# Prophesse_Sensor_v_1_5.net
KiCad netlist of a schematic drawn in Altium Designer
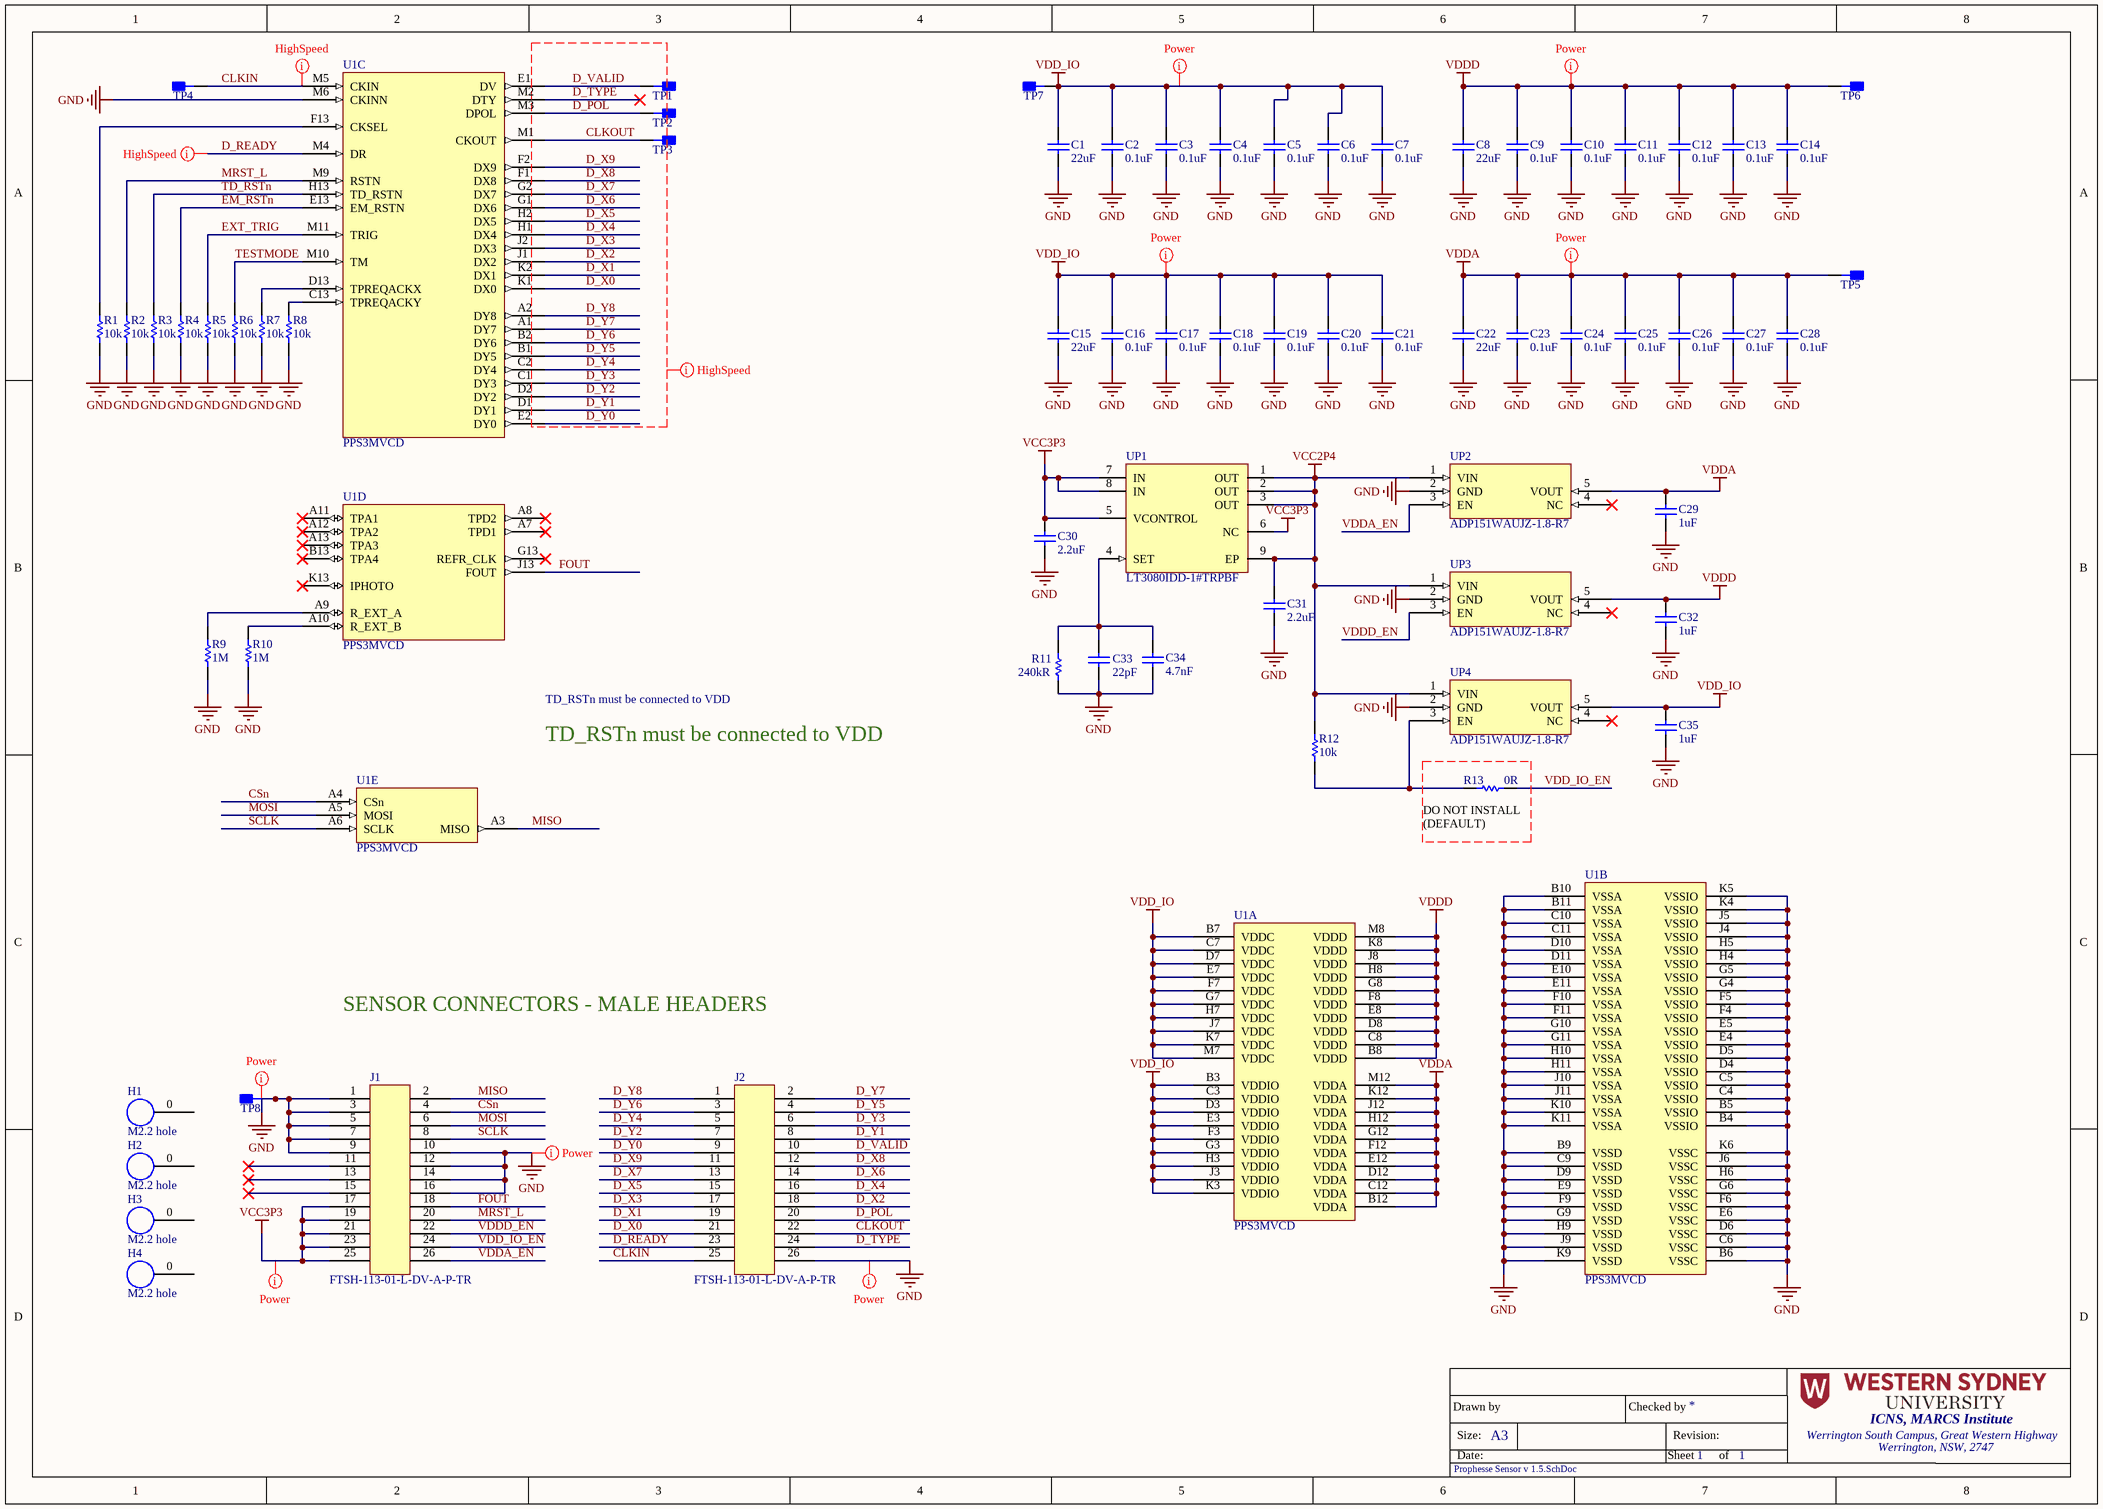
[diagram p0: Prophesse Sensor v 1.5.SchDoc]

(export (version "E")
  (design (tool "Eeschema 10.0.6"))
  (components
    (comp (ref "C1")
      (value "22uF")
      (footprint "CAP 0603 (1608)")
      (fields
        (field (name "MANUFACTURER") "Taiyo Yuden")
        (field (name "MANUFACTURER PART NUMBER") "LMK107BBJ226MA-T")
      )
      (libsource (lib "Falcon_Neuro") (part "LMK107BBJ226MA-T"))
    )
    (comp (ref "C2")
      (value "0.1uF")
      (footprint "CAP 0201 (0603)")
      (description "C0201C104K9PACTU, 0.1µF ±10% 6.3V Ceramic Capacitor X5R 0201 (0603 Metric)")
      (fields
        (field (name "MANUFACTURER") "KENET")
        (field (name "MANUFACTURER PART NUMBER") "C0201C104K9PACTU")
      )
      (libsource (lib "Falcon_Neuro") (part "C0201C104K9PACTU"))
    )
    (comp (ref "C3")
      (value "0.1uF")
      (footprint "CAP 0201 (0603)")
      (description "C0201C104K9PACTU, 0.1µF ±10% 6.3V Ceramic Capacitor X5R 0201 (0603 Metric)")
      (fields
        (field (name "MANUFACTURER") "KENET")
        (field (name "MANUFACTURER PART NUMBER") "C0201C104K9PACTU")
      )
      (libsource (lib "Falcon_Neuro") (part "C0201C104K9PACTU"))
    )
    (comp (ref "C4")
      (value "0.1uF")
      (footprint "CAP 0201 (0603)")
      (description "C0201C104K9PACTU, 0.1µF ±10% 6.3V Ceramic Capacitor X5R 0201 (0603 Metric)")
      (fields
        (field (name "MANUFACTURER") "KENET")
        (field (name "MANUFACTURER PART NUMBER") "C0201C104K9PACTU")
      )
      (libsource (lib "Falcon_Neuro") (part "C0201C104K9PACTU"))
    )
    (comp (ref "C5")
      (value "0.1uF")
      (footprint "CAP 0201 (0603)")
      (description "C0201C104K9PACTU, 0.1µF ±10% 6.3V Ceramic Capacitor X5R 0201 (0603 Metric)")
      (fields
        (field (name "MANUFACTURER") "KENET")
        (field (name "MANUFACTURER PART NUMBER") "C0201C104K9PACTU")
      )
      (libsource (lib "Falcon_Neuro") (part "C0201C104K9PACTU"))
    )
    (comp (ref "C6")
      (value "0.1uF")
      (footprint "CAP 0201 (0603)")
      (description "C0201C104K9PACTU, 0.1µF ±10% 6.3V Ceramic Capacitor X5R 0201 (0603 Metric)")
      (fields
        (field (name "MANUFACTURER") "KENET")
        (field (name "MANUFACTURER PART NUMBER") "C0201C104K9PACTU")
      )
      (libsource (lib "Falcon_Neuro") (part "C0201C104K9PACTU"))
    )
    (comp (ref "C7")
      (value "0.1uF")
      (footprint "CAP 0201 (0603)")
      (description "C0201C104K9PACTU, 0.1µF ±10% 6.3V Ceramic Capacitor X5R 0201 (0603 Metric)")
      (fields
        (field (name "MANUFACTURER") "KENET")
        (field (name "MANUFACTURER PART NUMBER") "C0201C104K9PACTU")
      )
      (libsource (lib "Falcon_Neuro") (part "C0201C104K9PACTU"))
    )
    (comp (ref "C8")
      (value "22uF")
      (footprint "CAP 0603 (1608)")
      (fields
        (field (name "MANUFACTURER") "Taiyo Yuden")
        (field (name "MANUFACTURER PART NUMBER") "LMK107BBJ226MA-T")
      )
      (libsource (lib "Falcon_Neuro") (part "LMK107BBJ226MA-T"))
    )
    (comp (ref "C9")
      (value "0.1uF")
      (footprint "CAP 0201 (0603)")
      (description "C0201C104K9PACTU, 0.1µF ±10% 6.3V Ceramic Capacitor X5R 0201 (0603 Metric)")
      (fields
        (field (name "MANUFACTURER") "KENET")
        (field (name "MANUFACTURER PART NUMBER") "C0201C104K9PACTU")
      )
      (libsource (lib "Falcon_Neuro") (part "C0201C104K9PACTU"))
    )
    (comp (ref "C10")
      (value "0.1uF")
      (footprint "CAP 0201 (0603)")
      (description "C0201C104K9PACTU, 0.1µF ±10% 6.3V Ceramic Capacitor X5R 0201 (0603 Metric)")
      (fields
        (field (name "MANUFACTURER") "KENET")
        (field (name "MANUFACTURER PART NUMBER") "C0201C104K9PACTU")
      )
      (libsource (lib "Falcon_Neuro") (part "C0201C104K9PACTU"))
    )
    (comp (ref "C11")
      (value "0.1uF")
      (footprint "CAP 0201 (0603)")
      (description "C0201C104K9PACTU, 0.1µF ±10% 6.3V Ceramic Capacitor X5R 0201 (0603 Metric)")
      (fields
        (field (name "MANUFACTURER") "KENET")
        (field (name "MANUFACTURER PART NUMBER") "C0201C104K9PACTU")
      )
      (libsource (lib "Falcon_Neuro") (part "C0201C104K9PACTU"))
    )
    (comp (ref "C12")
      (value "0.1uF")
      (footprint "CAP 0201 (0603)")
      (description "C0201C104K9PACTU, 0.1µF ±10% 6.3V Ceramic Capacitor X5R 0201 (0603 Metric)")
      (fields
        (field (name "MANUFACTURER") "KENET")
        (field (name "MANUFACTURER PART NUMBER") "C0201C104K9PACTU")
      )
      (libsource (lib "Falcon_Neuro") (part "C0201C104K9PACTU"))
    )
    (comp (ref "C13")
      (value "0.1uF")
      (footprint "CAP 0201 (0603)")
      (description "C0201C104K9PACTU, 0.1µF ±10% 6.3V Ceramic Capacitor X5R 0201 (0603 Metric)")
      (fields
        (field (name "MANUFACTURER") "KENET")
        (field (name "MANUFACTURER PART NUMBER") "C0201C104K9PACTU")
      )
      (libsource (lib "Falcon_Neuro") (part "C0201C104K9PACTU"))
    )
    (comp (ref "C14")
      (value "0.1uF")
      (footprint "CAP 0201 (0603)")
      (description "C0201C104K9PACTU, 0.1µF ±10% 6.3V Ceramic Capacitor X5R 0201 (0603 Metric)")
      (fields
        (field (name "MANUFACTURER") "KENET")
        (field (name "MANUFACTURER PART NUMBER") "C0201C104K9PACTU")
      )
      (libsource (lib "Falcon_Neuro") (part "C0201C104K9PACTU"))
    )
    (comp (ref "C15")
      (value "22uF")
      (footprint "CAP 0603 (1608)")
      (fields
        (field (name "MANUFACTURER") "Taiyo Yuden")
        (field (name "MANUFACTURER PART NUMBER") "LMK107BBJ226MA-T")
      )
      (libsource (lib "Falcon_Neuro") (part "LMK107BBJ226MA-T"))
    )
    (comp (ref "C16")
      (value "0.1uF")
      (footprint "CAP 0201 (0603)")
      (description "C0201C104K9PACTU, 0.1µF ±10% 6.3V Ceramic Capacitor X5R 0201 (0603 Metric)")
      (fields
        (field (name "MANUFACTURER") "KENET")
        (field (name "MANUFACTURER PART NUMBER") "C0201C104K9PACTU")
      )
      (libsource (lib "Falcon_Neuro") (part "C0201C104K9PACTU"))
    )
    (comp (ref "C17")
      (value "0.1uF")
      (footprint "CAP 0201 (0603)")
      (description "C0201C104K9PACTU, 0.1µF ±10% 6.3V Ceramic Capacitor X5R 0201 (0603 Metric)")
      (fields
        (field (name "MANUFACTURER") "KENET")
        (field (name "MANUFACTURER PART NUMBER") "C0201C104K9PACTU")
      )
      (libsource (lib "Falcon_Neuro") (part "C0201C104K9PACTU"))
    )
    (comp (ref "C18")
      (value "0.1uF")
      (footprint "CAP 0201 (0603)")
      (description "C0201C104K9PACTU, 0.1µF ±10% 6.3V Ceramic Capacitor X5R 0201 (0603 Metric)")
      (fields
        (field (name "MANUFACTURER") "KENET")
        (field (name "MANUFACTURER PART NUMBER") "C0201C104K9PACTU")
      )
      (libsource (lib "Falcon_Neuro") (part "C0201C104K9PACTU"))
    )
    (comp (ref "C19")
      (value "0.1uF")
      (footprint "CAP 0201 (0603)")
      (description "C0201C104K9PACTU, 0.1µF ±10% 6.3V Ceramic Capacitor X5R 0201 (0603 Metric)")
      (fields
        (field (name "MANUFACTURER") "KENET")
        (field (name "MANUFACTURER PART NUMBER") "C0201C104K9PACTU")
      )
      (libsource (lib "Falcon_Neuro") (part "C0201C104K9PACTU"))
    )
    (comp (ref "C20")
      (value "0.1uF")
      (footprint "CAP 0201 (0603)")
      (description "C0201C104K9PACTU, 0.1µF ±10% 6.3V Ceramic Capacitor X5R 0201 (0603 Metric)")
      (fields
        (field (name "MANUFACTURER") "KENET")
        (field (name "MANUFACTURER PART NUMBER") "C0201C104K9PACTU")
      )
      (libsource (lib "Falcon_Neuro") (part "C0201C104K9PACTU"))
    )
    (comp (ref "C21")
      (value "0.1uF")
      (footprint "CAP 0201 (0603)")
      (description "C0201C104K9PACTU, 0.1µF ±10% 6.3V Ceramic Capacitor X5R 0201 (0603 Metric)")
      (fields
        (field (name "MANUFACTURER") "KENET")
        (field (name "MANUFACTURER PART NUMBER") "C0201C104K9PACTU")
      )
      (libsource (lib "Falcon_Neuro") (part "C0201C104K9PACTU"))
    )
    (comp (ref "C22")
      (value "22uF")
      (footprint "CAP 0603 (1608)")
      (fields
        (field (name "MANUFACTURER") "Taiyo Yuden")
        (field (name "MANUFACTURER PART NUMBER") "LMK107BBJ226MA-T")
      )
      (libsource (lib "Falcon_Neuro") (part "LMK107BBJ226MA-T"))
    )
    (comp (ref "C23")
      (value "0.1uF")
      (footprint "CAP 0201 (0603)")
      (description "C0201C104K9PACTU, 0.1µF ±10% 6.3V Ceramic Capacitor X5R 0201 (0603 Metric)")
      (fields
        (field (name "MANUFACTURER") "KENET")
        (field (name "MANUFACTURER PART NUMBER") "C0201C104K9PACTU")
      )
      (libsource (lib "Falcon_Neuro") (part "C0201C104K9PACTU"))
    )
    (comp (ref "C24")
      (value "0.1uF")
      (footprint "CAP 0201 (0603)")
      (description "C0201C104K9PACTU, 0.1µF ±10% 6.3V Ceramic Capacitor X5R 0201 (0603 Metric)")
      (fields
        (field (name "MANUFACTURER") "KENET")
        (field (name "MANUFACTURER PART NUMBER") "C0201C104K9PACTU")
      )
      (libsource (lib "Falcon_Neuro") (part "C0201C104K9PACTU"))
    )
    (comp (ref "C25")
      (value "0.1uF")
      (footprint "CAP 0201 (0603)")
      (description "C0201C104K9PACTU, 0.1µF ±10% 6.3V Ceramic Capacitor X5R 0201 (0603 Metric)")
      (fields
        (field (name "MANUFACTURER") "KENET")
        (field (name "MANUFACTURER PART NUMBER") "C0201C104K9PACTU")
      )
      (libsource (lib "Falcon_Neuro") (part "C0201C104K9PACTU"))
    )
    (comp (ref "C26")
      (value "0.1uF")
      (footprint "CAP 0201 (0603)")
      (description "C0201C104K9PACTU, 0.1µF ±10% 6.3V Ceramic Capacitor X5R 0201 (0603 Metric)")
      (fields
        (field (name "MANUFACTURER") "KENET")
        (field (name "MANUFACTURER PART NUMBER") "C0201C104K9PACTU")
      )
      (libsource (lib "Falcon_Neuro") (part "C0201C104K9PACTU"))
    )
    (comp (ref "C27")
      (value "0.1uF")
      (footprint "CAP 0201 (0603)")
      (description "C0201C104K9PACTU, 0.1µF ±10% 6.3V Ceramic Capacitor X5R 0201 (0603 Metric)")
      (fields
        (field (name "MANUFACTURER") "KENET")
        (field (name "MANUFACTURER PART NUMBER") "C0201C104K9PACTU")
      )
      (libsource (lib "Falcon_Neuro") (part "C0201C104K9PACTU"))
    )
    (comp (ref "C28")
      (value "0.1uF")
      (footprint "CAP 0201 (0603)")
      (description "C0201C104K9PACTU, 0.1µF ±10% 6.3V Ceramic Capacitor X5R 0201 (0603 Metric)")
      (fields
        (field (name "MANUFACTURER") "KENET")
        (field (name "MANUFACTURER PART NUMBER") "C0201C104K9PACTU")
      )
      (libsource (lib "Falcon_Neuro") (part "C0201C104K9PACTU"))
    )
    (comp (ref "C29")
      (value "1uF")
      (footprint "CAP 0201 (0603)")
      (description "GRM033R60J105MEA2D, 1µF ±20% 6.3V Ceramic Capacitor X5R 0201 (0603 Metric)")
      (fields
        (field (name "MANUFACTURER") "Murata Electronics")
        (field (name "MANUFACTURER PART NUMBER") "GRM033R60J105MEA2D")
      )
      (libsource (lib "Falcon_Neuro") (part "GRM033R60J105MEA2D"))
    )
    (comp (ref "C30")
      (value "2.2uF")
      (footprint "CAP 0402 (1005)")
      (description "C0402C225K9PAC7867, 2.2µF ±10% 6.3V Ceramic Capacitor X5R 0402 (1005 Metric)")
      (fields
        (field (name "MANUFACTURER") "KEMET")
        (field (name "MANUFACTURER PART NUMBER") "C0402C225K9PAC7867")
      )
      (libsource (lib "Falcon_Neuro") (part "C0402C225K9PAC7867"))
    )
    (comp (ref "C31")
      (value "2.2uF")
      (footprint "CAP 0402 (1005)")
      (description "C0402C225K9PAC7867, 2.2µF ±10% 6.3V Ceramic Capacitor X5R 0402 (1005 Metric)")
      (fields
        (field (name "MANUFACTURER") "KEMET")
        (field (name "MANUFACTURER PART NUMBER") "C0402C225K9PAC7867")
      )
      (libsource (lib "Falcon_Neuro") (part "C0402C225K9PAC7867"))
    )
    (comp (ref "C32")
      (value "1uF")
      (footprint "CAP 0201 (0603)")
      (description "GRM033R60J105MEA2D, 1µF ±20% 6.3V Ceramic Capacitor X5R 0201 (0603 Metric)")
      (fields
        (field (name "MANUFACTURER") "Murata Electronics")
        (field (name "MANUFACTURER PART NUMBER") "GRM033R60J105MEA2D")
      )
      (libsource (lib "Falcon_Neuro") (part "GRM033R60J105MEA2D"))
    )
    (comp (ref "C33")
      (value "GRM1885C1H220JA01D")
      (footprint "CAP 0603 (1608)")
      (description "CAP CER 22PF 50V C0G/NP0 0603")
      (fields
        (field (name "MANUFACTURER") "Murata")
        (field (name "CAPACITANCE") "22pF")
        (field (name "TOLERANCE") "10%")
      )
      (libsource (lib "Falcon_Neuro") (part "GRM1885C1H220JA01D"))
    )
    (comp (ref "C34")
      (value "4.7nF")
      (footprint "CAP 0201 (0603)")
      (description "CC0201KRX7R6BB472, 4700pF ±10% 10V Ceramic Capacitor X7R 0201 (0603 Metric)")
      (fields
        (field (name "MANUFACTURER") "Yageo")
        (field (name "MANUFACTURER PART NUMBER") "CC0201KRX7R6BB472")
      )
      (libsource (lib "Falcon_Neuro") (part "CC0201KRX7R6BB472"))
    )
    (comp (ref "C35")
      (value "1uF")
      (footprint "CAP 0201 (0603)")
      (description "GRM033R60J105MEA2D, 1µF ±20% 6.3V Ceramic Capacitor X5R 0201 (0603 Metric)")
      (fields
        (field (name "MANUFACTURER") "Murata Electronics")
        (field (name "MANUFACTURER PART NUMBER") "GRM033R60J105MEA2D")
      )
      (libsource (lib "Falcon_Neuro") (part "GRM033R60J105MEA2D"))
    )
    (comp (ref "H1")
      (value "M2.2 hole")
      (footprint "M2.2 hole")
      (description "M2.2 through hole not plated")
      (libsource (lib "Falcon_Neuro") (part "M2.2 hole"))
    )
    (comp (ref "H2")
      (value "M2.2 hole")
      (footprint "M2.2 hole")
      (description "M2.2 through hole not plated")
      (libsource (lib "Falcon_Neuro") (part "M2.2 hole"))
    )
    (comp (ref "H3")
      (value "M2.2 hole")
      (footprint "M2.2 hole")
      (description "M2.2 through hole not plated")
      (libsource (lib "Falcon_Neuro") (part "M2.2 hole"))
    )
    (comp (ref "H4")
      (value "M2.2 hole")
      (footprint "M2.2 hole")
      (description "M2.2 through hole not plated")
      (libsource (lib "Falcon_Neuro") (part "M2.2 hole"))
    )
    (comp (ref "J1")
      (value "FTSH-113-01-L-DV-A-P-TR")
      (footprint "FTSH-113-01-L-DV-A")
      (description "Connector Header Surface Mount 26 position 0.050\" (1.27mm) 2 Rows Alignment Pin")
      (fields (field (name "MANUFACTURER") "Samtec"))
      (libsource (lib "Falcon_Neuro") (part "FTSH-113-01-L-DV-A-P-TR"))
    )
    (comp (ref "J2")
      (value "FTSH-113-01-L-DV-A-P-TR")
      (footprint "FTSH-113-01-L-DV-A")
      (description "Connector Header Surface Mount 26 position 0.050\" (1.27mm) 2 Rows Alignment Pin")
      (fields (field (name "MANUFACTURER") "Samtec"))
      (libsource (lib "Falcon_Neuro") (part "FTSH-113-01-L-DV-A-P-TR"))
    )
    (comp (ref "R1")
      (value "10k")
      (footprint "RES 0201 (0603)")
      (fields
        (field (name "MANUFACTURER PART NUMBER") "RK73H1HTTC1002F")
        (field (name "MANUFACTURER") "KOA Speer Electronics, Inc.")
      )
      (libsource (lib "Falcon_Neuro") (part "RK73H1HTTC1002F"))
    )
    (comp (ref "R2")
      (value "10k")
      (footprint "RES 0201 (0603)")
      (fields
        (field (name "MANUFACTURER PART NUMBER") "RK73H1HTTC1002F")
        (field (name "MANUFACTURER") "KOA Speer Electronics, Inc.")
      )
      (libsource (lib "Falcon_Neuro") (part "RK73H1HTTC1002F"))
    )
    (comp (ref "R3")
      (value "10k")
      (footprint "RES 0201 (0603)")
      (fields
        (field (name "MANUFACTURER PART NUMBER") "RK73H1HTTC1002F")
        (field (name "MANUFACTURER") "KOA Speer Electronics, Inc.")
      )
      (libsource (lib "Falcon_Neuro") (part "RK73H1HTTC1002F"))
    )
    (comp (ref "R4")
      (value "10k")
      (footprint "RES 0201 (0603)")
      (fields
        (field (name "MANUFACTURER PART NUMBER") "RK73H1HTTC1002F")
        (field (name "MANUFACTURER") "KOA Speer Electronics, Inc.")
      )
      (libsource (lib "Falcon_Neuro") (part "RK73H1HTTC1002F"))
    )
    (comp (ref "R5")
      (value "10k")
      (footprint "RES 0201 (0603)")
      (fields
        (field (name "MANUFACTURER PART NUMBER") "RK73H1HTTC1002F")
        (field (name "MANUFACTURER") "KOA Speer Electronics, Inc.")
      )
      (libsource (lib "Falcon_Neuro") (part "RK73H1HTTC1002F"))
    )
    (comp (ref "R6")
      (value "10k")
      (footprint "RES 0201 (0603)")
      (fields
        (field (name "MANUFACTURER PART NUMBER") "RK73H1HTTC1002F")
        (field (name "MANUFACTURER") "KOA Speer Electronics, Inc.")
      )
      (libsource (lib "Falcon_Neuro") (part "RK73H1HTTC1002F"))
    )
    (comp (ref "R7")
      (value "10k")
      (footprint "RES 0201 (0603)")
      (fields
        (field (name "MANUFACTURER PART NUMBER") "RK73H1HTTC1002F")
        (field (name "MANUFACTURER") "KOA Speer Electronics, Inc.")
      )
      (libsource (lib "Falcon_Neuro") (part "RK73H1HTTC1002F"))
    )
    (comp (ref "R8")
      (value "10k")
      (footprint "RES 0201 (0603)")
      (fields
        (field (name "MANUFACTURER PART NUMBER") "RK73H1HTTC1002F")
        (field (name "MANUFACTURER") "KOA Speer Electronics, Inc.")
      )
      (libsource (lib "Falcon_Neuro") (part "RK73H1HTTC1002F"))
    )
    (comp (ref "R9")
      (value "1M")
      (footprint "RES 0402 (1005)")
      (fields
        (field (name "MANUFACTURER PART NUMBER") "CRCW04021M00DHEDP")
        (field (name "MANUFACTURER") "Vishay Dale")
      )
      (libsource (lib "Falcon_Neuro") (part "CRCW04021M00DHEDP"))
    )
    (comp (ref "R10")
      (value "1M")
      (footprint "RES 0402 (1005)")
      (fields
        (field (name "MANUFACTURER PART NUMBER") "CRCW04021M00DHEDP")
        (field (name "MANUFACTURER") "Vishay Dale")
      )
      (libsource (lib "Falcon_Neuro") (part "CRCW04021M00DHEDP"))
    )
    (comp (ref "R11")
      (value "ERA-3AEB244V")
      (footprint "RES 0603 (1608)")
      (description "Res Thin Film 0603 240K Ohm 0.1% 1/10W ±25ppm/°C Molded SMD SMD Punched Carrier T/R")
      (fields
        (field (name "MANUFACTURER") "Panasonic")
        (field (name "TOLERANCE") "0.1%")
        (field (name "RESISTANCE") "240kR")
      )
      (libsource (lib "Falcon_Neuro") (part "ERA-3AEB244V"))
    )
    (comp (ref "R12")
      (value "10k")
      (footprint "RES 0201 (0603)")
      (fields
        (field (name "MANUFACTURER PART NUMBER") "RK73H1HTTC1002F")
        (field (name "MANUFACTURER") "KOA Speer Electronics, Inc.")
      )
      (libsource (lib "Falcon_Neuro") (part "RK73H1HTTC1002F"))
    )
    (comp (ref "R13")
      (value "0R")
      (footprint "RES 0402 (1005)")
      (fields
        (field (name "MANUFACTURER PART NUMBER") "RK73Z1ETTP")
        (field (name "MANUFACTURER") "KOA Speer Electronics, Inc.")
      )
      (libsource (lib "Falcon_Neuro") (part "RK73Z1ETTP"))
    )
    (comp (ref "TP1")
      (value "5015")
      (footprint "FP-5015-MFG")
      (description "PC TEST POINT MINIATURE SMT")
      (fields (field (name "MANUFACTURER") "Keystone Electronics"))
      (libsource (lib "") (part "5015_1"))
    )
    (comp (ref "TP2")
      (value "5015")
      (footprint "FP-5015-MFG")
      (description "PC TEST POINT MINIATURE SMT")
      (fields (field (name "MANUFACTURER") "Keystone Electronics"))
      (libsource (lib "") (part "5015_1"))
    )
    (comp (ref "TP3")
      (value "5015")
      (footprint "FP-5015-MFG")
      (description "PC TEST POINT MINIATURE SMT")
      (fields (field (name "MANUFACTURER") "Keystone Electronics"))
      (libsource (lib "") (part "5015_1"))
    )
    (comp (ref "TP4")
      (value "5015")
      (footprint "FP-5015-MFG")
      (description "PC TEST POINT MINIATURE SMT")
      (fields (field (name "MANUFACTURER") "Keystone Electronics"))
      (libsource (lib "Falcon_Neuro") (part "5015"))
    )
    (comp (ref "TP5")
      (value "5015")
      (footprint "FP-5015-MFG")
      (description "PC TEST POINT MINIATURE SMT")
      (fields (field (name "MANUFACTURER") "Keystone Electronics"))
      (libsource (lib "") (part "5015_1"))
    )
    (comp (ref "TP6")
      (value "5015")
      (footprint "FP-5015-MFG")
      (description "PC TEST POINT MINIATURE SMT")
      (fields (field (name "MANUFACTURER") "Keystone Electronics"))
      (libsource (lib "") (part "5015_1"))
    )
    (comp (ref "TP7")
      (value "5015")
      (footprint "FP-5015-MFG")
      (description "PC TEST POINT MINIATURE SMT")
      (fields (field (name "MANUFACTURER") "Keystone Electronics"))
      (libsource (lib "Falcon_Neuro") (part "5015"))
    )
    (comp (ref "TP8")
      (value "5015")
      (footprint "FP-5015-MFG")
      (description "PC TEST POINT MINIATURE SMT")
      (fields (field (name "MANUFACTURER") "Keystone Electronics"))
      (libsource (lib "Falcon_Neuro") (part "5015"))
    )
    (comp (ref "U1")
      (value "PPS3MVCD")
      (footprint "BPGA142C100P13X11_1500X1300X223_PSS3MVCD")
      (description "Prophesse Sensor V3M")
      (fields (field (name "MANUFACTURER") "Prophesse"))
      (libsource (lib "Falcon_Neuro") (part "PPS3MVCD"))
    )
    (comp (ref "UP1")
      (value "LT3080IDD-1#TRPBF")
      (footprint "LT-DD-8_V")
      (description "Linear Voltage Regulator IC Positive Adjustable 1 Output 1.1A 8-DFN (3x3)")
      (fields (field (name "MANUFACTURER") "Analog Devices / Linear Technology"))
      (libsource (lib "ICNS_PropheseeLib") (part "LT3080IDD-1#TRPBF"))
    )
    (comp (ref "UP2")
      (value "ADP151WAUJZ-1.8-R7")
      (footprint "SOT95P280X100-5N")
      (description "LDO Regulator Pos 1.8V 0.2A Automotive 5-Pin TSOT T/R")
      (fields (field (name "MANUFACTURER") "Analog Devices"))
      (libsource (lib "Falcon_Neuro") (part "ADP151WAUJZ-1.8-R7"))
    )
    (comp (ref "UP3")
      (value "ADP151WAUJZ-1.8-R7")
      (footprint "SOT95P280X100-5N")
      (description "LDO Regulator Pos 1.8V 0.2A Automotive 5-Pin TSOT T/R")
      (fields (field (name "MANUFACTURER") "Analog Devices"))
      (libsource (lib "Falcon_Neuro") (part "ADP151WAUJZ-1.8-R7"))
    )
    (comp (ref "UP4")
      (value "ADP151WAUJZ-1.8-R7")
      (footprint "SOT95P280X100-5N")
      (description "LDO Regulator Pos 1.8V 0.2A Automotive 5-Pin TSOT T/R")
      (fields (field (name "MANUFACTURER") "Analog Devices"))
      (libsource (lib "Falcon_Neuro") (part "ADP151WAUJZ-1.8-R7"))
    )
  )
  (nets
    (net (code "1") (name "/CLKIN") (class "Default")
      (node (ref "J2") (pin "25") (pintype "passive"))
      (node (ref "TP4") (pin "1") (pinfunction "1_1") (pintype "passive"))
      (node (ref "U1") (pin "M5") (pinfunction "CKIN_M5") (pintype "input"))
    )
    (net (code "2") (name "/CLKOUT") (class "Default")
      (node (ref "J2") (pin "22") (pintype "passive"))
      (node (ref "TP3") (pin "1") (pinfunction "1_1") (pintype "passive"))
      (node (ref "U1") (pin "M1") (pinfunction "CKOUT_M1") (pintype "output"))
    )
    (net (code "3") (name "/CSn") (class "Default")
      (node (ref "J1") (pin "4") (pintype "passive"))
      (node (ref "U1") (pin "A4") (pinfunction "CSn_A4") (pintype "input"))
    )
    (net (code "4") (name "/D_POL") (class "Default")
      (node (ref "J2") (pin "20") (pintype "passive"))
      (node (ref "TP2") (pin "1") (pinfunction "1_1") (pintype "passive"))
      (node (ref "U1") (pin "M3") (pinfunction "DPOL_M3") (pintype "output"))
    )
    (net (code "5") (name "/D_READY") (class "Default")
      (node (ref "J2") (pin "23") (pintype "passive"))
      (node (ref "U1") (pin "M4") (pinfunction "DR_M4") (pintype "input"))
    )
    (net (code "6") (name "/D_TYPE") (class "Default")
      (node (ref "J2") (pin "24") (pintype "passive"))
      (node (ref "U1") (pin "M2") (pinfunction "DTY_M2") (pintype "output"))
    )
    (net (code "7") (name "/D_VALID") (class "Default")
      (node (ref "J2") (pin "10") (pintype "passive"))
      (node (ref "TP1") (pin "1") (pinfunction "1_1") (pintype "passive"))
      (node (ref "U1") (pin "E1") (pinfunction "DV_E1") (pintype "output"))
    )
    (net (code "8") (name "/D_X0") (class "Default")
      (node (ref "J2") (pin "21") (pintype "passive"))
      (node (ref "U1") (pin "K1") (pinfunction "DX0_K1") (pintype "output"))
    )
    (net (code "9") (name "/D_X1") (class "Default")
      (node (ref "J2") (pin "19") (pintype "passive"))
      (node (ref "U1") (pin "K2") (pinfunction "DX1_K2") (pintype "output"))
    )
    (net (code "10") (name "/D_X2") (class "Default")
      (node (ref "J2") (pin "18") (pintype "passive"))
      (node (ref "U1") (pin "J1") (pinfunction "DX2_J1") (pintype "output"))
    )
    (net (code "11") (name "/D_X3") (class "Default")
      (node (ref "J2") (pin "17") (pintype "passive"))
      (node (ref "U1") (pin "J2") (pinfunction "DX3_J2") (pintype "output"))
    )
    (net (code "12") (name "/D_X4") (class "Default")
      (node (ref "J2") (pin "16") (pintype "passive"))
      (node (ref "U1") (pin "H1") (pinfunction "DX4_H1") (pintype "output"))
    )
    (net (code "13") (name "/D_X5") (class "Default")
      (node (ref "J2") (pin "15") (pintype "passive"))
      (node (ref "U1") (pin "H2") (pinfunction "DX5_H2") (pintype "output"))
    )
    (net (code "14") (name "/D_X6") (class "Default")
      (node (ref "J2") (pin "14") (pintype "passive"))
      (node (ref "U1") (pin "G1") (pinfunction "DX6_G1") (pintype "output"))
    )
    (net (code "15") (name "/D_X7") (class "Default")
      (node (ref "J2") (pin "13") (pintype "passive"))
      (node (ref "U1") (pin "G2") (pinfunction "DX7_G2") (pintype "output"))
    )
    (net (code "16") (name "/D_X8") (class "Default")
      (node (ref "J2") (pin "12") (pintype "passive"))
      (node (ref "U1") (pin "F1") (pinfunction "DX8_F1") (pintype "output"))
    )
    (net (code "17") (name "/D_X9") (class "Default")
      (node (ref "J2") (pin "11") (pintype "passive"))
      (node (ref "U1") (pin "F2") (pinfunction "DX9_F2") (pintype "output"))
    )
    (net (code "18") (name "/D_Y0") (class "Default")
      (node (ref "J2") (pin "9") (pintype "passive"))
      (node (ref "U1") (pin "E2") (pinfunction "DY0_E2") (pintype "output"))
    )
    (net (code "19") (name "/D_Y1") (class "Default")
      (node (ref "J2") (pin "8") (pintype "passive"))
      (node (ref "U1") (pin "D1") (pinfunction "DY1_D1") (pintype "output"))
    )
    (net (code "20") (name "/D_Y2") (class "Default")
      (node (ref "J2") (pin "7") (pintype "passive"))
      (node (ref "U1") (pin "D2") (pinfunction "DY2_D2") (pintype "output"))
    )
    (net (code "21") (name "/D_Y3") (class "Default")
      (node (ref "J2") (pin "6") (pintype "passive"))
      (node (ref "U1") (pin "C1") (pinfunction "DY3_C1") (pintype "output"))
    )
    (net (code "22") (name "/D_Y4") (class "Default")
      (node (ref "J2") (pin "5") (pintype "passive"))
      (node (ref "U1") (pin "C2") (pinfunction "DY4_C2") (pintype "output"))
    )
    (net (code "23") (name "/D_Y5") (class "Default")
      (node (ref "J2") (pin "4") (pintype "passive"))
      (node (ref "U1") (pin "B1") (pinfunction "DY5_B1") (pintype "output"))
    )
    (net (code "24") (name "/D_Y6") (class "Default")
      (node (ref "J2") (pin "3") (pintype "passive"))
      (node (ref "U1") (pin "B2") (pinfunction "DY6_B2") (pintype "output"))
    )
    (net (code "25") (name "/D_Y7") (class "Default")
      (node (ref "J2") (pin "2") (pintype "passive"))
      (node (ref "U1") (pin "A1") (pinfunction "DY7_A1") (pintype "output"))
    )
    (net (code "26") (name "/D_Y8") (class "Default")
      (node (ref "J2") (pin "1") (pintype "passive"))
      (node (ref "U1") (pin "A2") (pinfunction "DY8_A2") (pintype "output"))
    )
    (net (code "27") (name "/EM_RSTn") (class "Default")
      (node (ref "R4") (pin "2") (pinfunction "2_2") (pintype "passive"))
      (node (ref "U1") (pin "E13") (pinfunction "EM_RSTN_E13") (pintype "input"))
    )
    (net (code "28") (name "/EXT_TRIG") (class "Default")
      (node (ref "R5") (pin "2") (pinfunction "2_2") (pintype "passive"))
      (node (ref "U1") (pin "M11") (pinfunction "TRIG_M11") (pintype "input"))
    )
    (net (code "29") (name "/FOUT") (class "Default")
      (node (ref "J1") (pin "18") (pintype "passive"))
      (node (ref "U1") (pin "J13") (pinfunction "FOUT_J13") (pintype "output"))
    )
    (net (code "30") (name "/MISO") (class "Default")
      (node (ref "J1") (pin "2") (pintype "passive"))
      (node (ref "U1") (pin "A3") (pinfunction "MISO_A3") (pintype "output"))
    )
    (net (code "31") (name "/MOSI") (class "Default")
      (node (ref "J1") (pin "6") (pintype "passive"))
      (node (ref "U1") (pin "A5") (pinfunction "MOSI_A5") (pintype "input"))
    )
    (net (code "32") (name "/MRST_L") (class "Default")
      (node (ref "J1") (pin "20") (pintype "passive"))
      (node (ref "R2") (pin "2") (pinfunction "2_2") (pintype "passive"))
      (node (ref "U1") (pin "M9") (pinfunction "RSTN_M9") (pintype "input"))
    )
    (net (code "33") (name "/SCLK") (class "Default")
      (node (ref "J1") (pin "8") (pintype "passive"))
      (node (ref "U1") (pin "A6") (pinfunction "SCLK_A6") (pintype "input"))
    )
    (net (code "34") (name "/TD_RSTn") (class "Default")
      (node (ref "R3") (pin "2") (pinfunction "2_2") (pintype "passive"))
      (node (ref "U1") (pin "H13") (pinfunction "TD_RSTN_H13") (pintype "input"))
    )
    (net (code "35") (name "/TESTMODE") (class "Default")
      (node (ref "R6") (pin "2") (pinfunction "2_2") (pintype "passive"))
      (node (ref "U1") (pin "M10") (pinfunction "TM_M10") (pintype "input"))
    )
    (net (code "36") (name "/VDDA_EN") (class "Default")
      (node (ref "J1") (pin "26") (pintype "passive"))
      (node (ref "UP2") (pin "3") (pinfunction "EN_3") (pintype "input"))
    )
    (net (code "37") (name "/VDDD_EN") (class "Default")
      (node (ref "J1") (pin "22") (pintype "passive"))
      (node (ref "UP3") (pin "3") (pinfunction "EN_3") (pintype "input"))
    )
    (net (code "38") (name "/VDD_IO_EN") (class "Default")
      (node (ref "J1") (pin "24") (pintype "passive"))
      (node (ref "R13") (pin "2") (pinfunction "2_2") (pintype "passive"))
    )
    (net (code "39") (name "GND") (class "Default")
      (node (ref "C1") (pin "1") (pinfunction "1_1") (pintype "passive"))
      (node (ref "C10") (pin "1") (pinfunction "1_1") (pintype "passive"))
      (node (ref "C11") (pin "1") (pinfunction "1_1") (pintype "passive"))
      (node (ref "C12") (pin "1") (pinfunction "1_1") (pintype "passive"))
      (node (ref "C13") (pin "1") (pinfunction "1_1") (pintype "passive"))
      (node (ref "C14") (pin "1") (pinfunction "1_1") (pintype "passive"))
      (node (ref "C15") (pin "1") (pinfunction "1_1") (pintype "passive"))
      (node (ref "C16") (pin "1") (pinfunction "1_1") (pintype "passive"))
      (node (ref "C17") (pin "1") (pinfunction "1_1") (pintype "passive"))
      (node (ref "C18") (pin "1") (pinfunction "1_1") (pintype "passive"))
      (node (ref "C19") (pin "1") (pinfunction "1_1") (pintype "passive"))
      (node (ref "C2") (pin "1") (pinfunction "1_1") (pintype "passive"))
      (node (ref "C20") (pin "1") (pinfunction "1_1") (pintype "passive"))
      (node (ref "C21") (pin "1") (pinfunction "1_1") (pintype "passive"))
      (node (ref "C22") (pin "1") (pinfunction "1_1") (pintype "passive"))
      (node (ref "C23") (pin "1") (pinfunction "1_1") (pintype "passive"))
      (node (ref "C24") (pin "1") (pinfunction "1_1") (pintype "passive"))
      (node (ref "C25") (pin "1") (pinfunction "1_1") (pintype "passive"))
      (node (ref "C26") (pin "1") (pinfunction "1_1") (pintype "passive"))
      (node (ref "C27") (pin "1") (pinfunction "1_1") (pintype "passive"))
      (node (ref "C28") (pin "1") (pinfunction "1_1") (pintype "passive"))
      (node (ref "C29") (pin "1") (pinfunction "1_1") (pintype "passive"))
      (node (ref "C3") (pin "1") (pinfunction "1_1") (pintype "passive"))
      (node (ref "C30") (pin "2") (pinfunction "2_2") (pintype "passive"))
      (node (ref "C31") (pin "2") (pinfunction "2_2") (pintype "passive"))
      (node (ref "C32") (pin "1") (pinfunction "1_1") (pintype "passive"))
      (node (ref "C33") (pin "2") (pinfunction "2_2") (pintype "passive"))
      (node (ref "C34") (pin "2") (pinfunction "2_2") (pintype "passive"))
      (node (ref "C35") (pin "1") (pinfunction "1_1") (pintype "passive"))
      (node (ref "C4") (pin "1") (pinfunction "1_1") (pintype "passive"))
      (node (ref "C5") (pin "1") (pinfunction "1_1") (pintype "passive"))
      (node (ref "C6") (pin "1") (pinfunction "1_1") (pintype "passive"))
      (node (ref "C7") (pin "1") (pinfunction "1_1") (pintype "passive"))
      (node (ref "C8") (pin "1") (pinfunction "1_1") (pintype "passive"))
      (node (ref "C9") (pin "1") (pinfunction "1_1") (pintype "passive"))
      (node (ref "J1") (pin "1") (pintype "passive"))
      (node (ref "J1") (pin "10") (pintype "passive"))
      (node (ref "J1") (pin "12") (pintype "passive"))
      (node (ref "J1") (pin "14") (pintype "passive"))
      (node (ref "J1") (pin "16") (pintype "passive"))
      (node (ref "J1") (pin "3") (pintype "passive"))
      (node (ref "J1") (pin "5") (pintype "passive"))
      (node (ref "J1") (pin "7") (pintype "passive"))
      (node (ref "J1") (pin "9") (pintype "passive"))
      (node (ref "J2") (pin "26") (pintype "passive"))
      (node (ref "R1") (pin "1") (pinfunction "1_1") (pintype "passive"))
      (node (ref "R10") (pin "2") (pinfunction "2_2") (pintype "passive"))
      (node (ref "R11") (pin "2") (pinfunction "2_2") (pintype "passive"))
      (node (ref "R2") (pin "1") (pinfunction "1_1") (pintype "passive"))
      (node (ref "R3") (pin "1") (pinfunction "1_1") (pintype "passive"))
      (node (ref "R4") (pin "1") (pinfunction "1_1") (pintype "passive"))
      (node (ref "R5") (pin "1") (pinfunction "1_1") (pintype "passive"))
      (node (ref "R6") (pin "1") (pinfunction "1_1") (pintype "passive"))
      (node (ref "R7") (pin "1") (pinfunction "1_1") (pintype "passive"))
      (node (ref "R8") (pin "1") (pinfunction "1_1") (pintype "passive"))
      (node (ref "R9") (pin "1") (pinfunction "1_1") (pintype "passive"))
      (node (ref "TP8") (pin "1") (pinfunction "1_1") (pintype "passive"))
      (node (ref "U1") (pin "B10") (pinfunction "VSSA_B10") (pintype "power_in"))
      (node (ref "U1") (pin "B11") (pinfunction "VSSA_B11") (pintype "power_in"))
      (node (ref "U1") (pin "B4") (pinfunction "VSSIO_B4") (pintype "power_in"))
      (node (ref "U1") (pin "B5") (pinfunction "VSSIO_B5") (pintype "power_in"))
      (node (ref "U1") (pin "B6") (pinfunction "VSSC_B6") (pintype "power_in"))
      (node (ref "U1") (pin "B9") (pinfunction "VSSD_B9") (pintype "power_in"))
      (node (ref "U1") (pin "C10") (pinfunction "VSSA_C10") (pintype "power_in"))
      (node (ref "U1") (pin "C11") (pinfunction "VSSA_C11") (pintype "power_in"))
      (node (ref "U1") (pin "C4") (pinfunction "VSSIO_C4") (pintype "power_in"))
      (node (ref "U1") (pin "C5") (pinfunction "VSSIO_C5") (pintype "power_in"))
      (node (ref "U1") (pin "C6") (pinfunction "VSSC_C6") (pintype "power_in"))
      (node (ref "U1") (pin "C9") (pinfunction "VSSD_C9") (pintype "power_in"))
      (node (ref "U1") (pin "D10") (pinfunction "VSSA_D10") (pintype "power_in"))
      (node (ref "U1") (pin "D11") (pinfunction "VSSA_D11") (pintype "power_in"))
      (node (ref "U1") (pin "D4") (pinfunction "VSSIO_D4") (pintype "power_in"))
      (node (ref "U1") (pin "D5") (pinfunction "VSSIO_D5") (pintype "power_in"))
      (node (ref "U1") (pin "D6") (pinfunction "VSSC_D6") (pintype "power_in"))
      (node (ref "U1") (pin "D9") (pinfunction "VSSD_D9") (pintype "power_in"))
      (node (ref "U1") (pin "E10") (pinfunction "VSSA_E10") (pintype "power_in"))
      (node (ref "U1") (pin "E11") (pinfunction "VSSA_E11") (pintype "power_in"))
      (node (ref "U1") (pin "E4") (pinfunction "VSSIO_E4") (pintype "power_in"))
      (node (ref "U1") (pin "E5") (pinfunction "VSSIO_E5") (pintype "power_in"))
      (node (ref "U1") (pin "E6") (pinfunction "VSSC_E6") (pintype "power_in"))
      (node (ref "U1") (pin "E9") (pinfunction "VSSD_E9") (pintype "power_in"))
      (node (ref "U1") (pin "F10") (pinfunction "VSSA_F10") (pintype "power_in"))
      (node (ref "U1") (pin "F11") (pinfunction "VSSA_F11") (pintype "power_in"))
      (node (ref "U1") (pin "F4") (pinfunction "VSSIO_F4") (pintype "power_in"))
      (node (ref "U1") (pin "F5") (pinfunction "VSSIO_F5") (pintype "power_in"))
      (node (ref "U1") (pin "F6") (pinfunction "VSSC_F6") (pintype "power_in"))
      (node (ref "U1") (pin "F9") (pinfunction "VSSD_F9") (pintype "power_in"))
      (node (ref "U1") (pin "G10") (pinfunction "VSSA_G10") (pintype "power_in"))
      (node (ref "U1") (pin "G11") (pinfunction "VSSA_G11") (pintype "power_in"))
      (node (ref "U1") (pin "G4") (pinfunction "VSSIO_G4") (pintype "power_in"))
      (node (ref "U1") (pin "G5") (pinfunction "VSSIO_G5") (pintype "power_in"))
      (node (ref "U1") (pin "G6") (pinfunction "VSSC_G6") (pintype "power_in"))
      (node (ref "U1") (pin "G9") (pinfunction "VSSD_G9") (pintype "power_in"))
      (node (ref "U1") (pin "H10") (pinfunction "VSSA_H10") (pintype "power_in"))
      (node (ref "U1") (pin "H11") (pinfunction "VSSA_H11") (pintype "power_in"))
      (node (ref "U1") (pin "H4") (pinfunction "VSSIO_H4") (pintype "power_in"))
      (node (ref "U1") (pin "H5") (pinfunction "VSSIO_H5") (pintype "power_in"))
      (node (ref "U1") (pin "H6") (pinfunction "VSSC_H6") (pintype "power_in"))
      (node (ref "U1") (pin "H9") (pinfunction "VSSD_H9") (pintype "power_in"))
      (node (ref "U1") (pin "J10") (pinfunction "VSSA_J10") (pintype "power_in"))
      (node (ref "U1") (pin "J11") (pinfunction "VSSA_J11") (pintype "power_in"))
      (node (ref "U1") (pin "J4") (pinfunction "VSSIO_J4") (pintype "power_in"))
      (node (ref "U1") (pin "J5") (pinfunction "VSSIO_J5") (pintype "power_in"))
      (node (ref "U1") (pin "J6") (pinfunction "VSSC_J6") (pintype "power_in"))
      (node (ref "U1") (pin "J9") (pinfunction "VSSD_J9") (pintype "power_in"))
      (node (ref "U1") (pin "K10") (pinfunction "VSSA_K10") (pintype "power_in"))
      (node (ref "U1") (pin "K11") (pinfunction "VSSA_K11") (pintype "power_in"))
      (node (ref "U1") (pin "K4") (pinfunction "VSSIO_K4") (pintype "power_in"))
      (node (ref "U1") (pin "K5") (pinfunction "VSSIO_K5") (pintype "power_in"))
      (node (ref "U1") (pin "K6") (pinfunction "VSSC_K6") (pintype "power_in"))
      (node (ref "U1") (pin "K9") (pinfunction "VSSD_K9") (pintype "power_in"))
      (node (ref "U1") (pin "M6") (pinfunction "CKINN_M6") (pintype "input"))
      (node (ref "UP2") (pin "2") (pinfunction "GND_2") (pintype "input"))
      (node (ref "UP3") (pin "2") (pinfunction "GND_2") (pintype "input"))
      (node (ref "UP4") (pin "2") (pinfunction "GND_2") (pintype "input"))
    )
    (net (code "40") (name "Net-(U1C-CKSEL)") (class "Default")
      (node (ref "R1") (pin "2") (pinfunction "2_2") (pintype "passive"))
      (node (ref "U1") (pin "F13") (pinfunction "CKSEL_F13") (pintype "input"))
    )
    (net (code "41") (name "Net-(U1C-TPREQACKX)") (class "Default")
      (node (ref "R7") (pin "2") (pinfunction "2_2") (pintype "passive"))
      (node (ref "U1") (pin "D13") (pinfunction "TPREQACKX_D13") (pintype "input"))
    )
    (net (code "42") (name "Net-(U1C-TPREQACKY)") (class "Default")
      (node (ref "R8") (pin "2") (pinfunction "2_2") (pintype "passive"))
      (node (ref "U1") (pin "C13") (pinfunction "TPREQACKY_C13") (pintype "input"))
    )
    (net (code "43") (name "Net-(U1D-R_EXT_A)") (class "Default")
      (node (ref "R9") (pin "2") (pinfunction "2_2") (pintype "passive"))
      (node (ref "U1") (pin "A9") (pinfunction "R_EXT_A_A9") (pintype "bidirectional"))
    )
    (net (code "44") (name "Net-(U1D-R_EXT_B)") (class "Default")
      (node (ref "R10") (pin "1") (pinfunction "1_1") (pintype "passive"))
      (node (ref "U1") (pin "A10") (pinfunction "R_EXT_B_A10") (pintype "bidirectional"))
    )
    (net (code "45") (name "Net-(UP1-SET)") (class "Default")
      (node (ref "C33") (pin "1") (pinfunction "1_1") (pintype "passive"))
      (node (ref "C34") (pin "1") (pinfunction "1_1") (pintype "passive"))
      (node (ref "R11") (pin "1") (pinfunction "1_1") (pintype "passive"))
      (node (ref "UP1") (pin "4") (pinfunction "SET_4") (pintype "input"))
    )
    (net (code "46") (name "Net-(UP4-EN)") (class "Default")
      (node (ref "R12") (pin "1") (pinfunction "1_1") (pintype "passive"))
      (node (ref "R13") (pin "1") (pinfunction "1_1") (pintype "passive"))
      (node (ref "UP4") (pin "3") (pinfunction "EN_3") (pintype "input"))
    )
    (net (code "47") (name "VCC2P4") (class "Default")
      (node (ref "C31") (pin "1") (pinfunction "1_1") (pintype "passive"))
      (node (ref "R12") (pin "2") (pinfunction "2_2") (pintype "passive"))
      (node (ref "UP1") (pin "1") (pinfunction "OUT_1") (pintype "power_in"))
      (node (ref "UP1") (pin "2") (pinfunction "OUT_2") (pintype "power_in"))
      (node (ref "UP1") (pin "3") (pinfunction "OUT_3") (pintype "power_in"))
      (node (ref "UP1") (pin "9") (pinfunction "EP_9") (pintype "power_in"))
      (node (ref "UP2") (pin "1") (pinfunction "VIN_1") (pintype "input"))
      (node (ref "UP3") (pin "1") (pinfunction "VIN_1") (pintype "input"))
      (node (ref "UP4") (pin "1") (pinfunction "VIN_1") (pintype "input"))
    )
    (net (code "48") (name "VCC3P3") (class "Default")
      (node (ref "C30") (pin "1") (pinfunction "1_1") (pintype "passive"))
      (node (ref "J1") (pin "17") (pintype "passive"))
      (node (ref "J1") (pin "19") (pintype "passive"))
      (node (ref "J1") (pin "21") (pintype "passive"))
      (node (ref "J1") (pin "23") (pintype "passive"))
      (node (ref "J1") (pin "25") (pintype "passive"))
      (node (ref "UP1") (pin "5") (pinfunction "VCONTROL_5") (pintype "power_in"))
      (node (ref "UP1") (pin "6") (pinfunction "NC_6") (pintype "passive"))
      (node (ref "UP1") (pin "7") (pinfunction "IN_7") (pintype "power_in"))
      (node (ref "UP1") (pin "8") (pinfunction "IN_8") (pintype "power_in"))
    )
    (net (code "49") (name "VDDA") (class "Default")
      (node (ref "C22") (pin "2") (pinfunction "2_2") (pintype "passive"))
      (node (ref "C23") (pin "2") (pinfunction "2_2") (pintype "passive"))
      (node (ref "C24") (pin "2") (pinfunction "2_2") (pintype "passive"))
      (node (ref "C25") (pin "2") (pinfunction "2_2") (pintype "passive"))
      (node (ref "C26") (pin "2") (pinfunction "2_2") (pintype "passive"))
      (node (ref "C27") (pin "2") (pinfunction "2_2") (pintype "passive"))
      (node (ref "C28") (pin "2") (pinfunction "2_2") (pintype "passive"))
      (node (ref "C29") (pin "2") (pinfunction "2_2") (pintype "passive"))
      (node (ref "TP5") (pin "1") (pinfunction "1_1") (pintype "passive"))
      (node (ref "U1") (pin "B12") (pinfunction "VDDA_B12") (pintype "power_in"))
      (node (ref "U1") (pin "C12") (pinfunction "VDDA_C12") (pintype "power_in"))
      (node (ref "U1") (pin "D12") (pinfunction "VDDA_D12") (pintype "power_in"))
      (node (ref "U1") (pin "E12") (pinfunction "VDDA_E12") (pintype "power_in"))
      (node (ref "U1") (pin "F12") (pinfunction "VDDA_F12") (pintype "power_in"))
      (node (ref "U1") (pin "G12") (pinfunction "VDDA_G12") (pintype "power_in"))
      (node (ref "U1") (pin "H12") (pinfunction "VDDA_H12") (pintype "power_in"))
      (node (ref "U1") (pin "J12") (pinfunction "VDDA_J12") (pintype "power_in"))
      (node (ref "U1") (pin "K12") (pinfunction "VDDA_K12") (pintype "power_in"))
      (node (ref "U1") (pin "M12") (pinfunction "VDDA_M12") (pintype "power_in"))
      (node (ref "UP2") (pin "5") (pinfunction "VOUT_5") (pintype "input"))
    )
    (net (code "50") (name "VDDD") (class "Default")
      (node (ref "C10") (pin "2") (pinfunction "2_2") (pintype "passive"))
      (node (ref "C11") (pin "2") (pinfunction "2_2") (pintype "passive"))
      (node (ref "C12") (pin "2") (pinfunction "2_2") (pintype "passive"))
      (node (ref "C13") (pin "2") (pinfunction "2_2") (pintype "passive"))
      (node (ref "C14") (pin "2") (pinfunction "2_2") (pintype "passive"))
      (node (ref "C32") (pin "2") (pinfunction "2_2") (pintype "passive"))
      (node (ref "C8") (pin "2") (pinfunction "2_2") (pintype "passive"))
      (node (ref "C9") (pin "2") (pinfunction "2_2") (pintype "passive"))
      (node (ref "TP6") (pin "1") (pinfunction "1_1") (pintype "passive"))
      (node (ref "U1") (pin "B8") (pinfunction "VDDD_B8") (pintype "power_in"))
      (node (ref "U1") (pin "C8") (pinfunction "VDDD_C8") (pintype "power_in"))
      (node (ref "U1") (pin "D8") (pinfunction "VDDD_D8") (pintype "power_in"))
      (node (ref "U1") (pin "E8") (pinfunction "VDDD_E8") (pintype "power_in"))
      (node (ref "U1") (pin "F8") (pinfunction "VDDD_F8") (pintype "power_in"))
      (node (ref "U1") (pin "G8") (pinfunction "VDDD_G8") (pintype "power_in"))
      (node (ref "U1") (pin "H8") (pinfunction "VDDD_H8") (pintype "power_in"))
      (node (ref "U1") (pin "J8") (pinfunction "VDDD_J8") (pintype "power_in"))
      (node (ref "U1") (pin "K8") (pinfunction "VDDD_K8") (pintype "power_in"))
      (node (ref "U1") (pin "M8") (pinfunction "VDDD_M8") (pintype "power_in"))
      (node (ref "UP3") (pin "5") (pinfunction "VOUT_5") (pintype "input"))
    )
    (net (code "51") (name "VDD_IO") (class "Default")
      (node (ref "C1") (pin "2") (pinfunction "2_2") (pintype "passive"))
      (node (ref "C15") (pin "2") (pinfunction "2_2") (pintype "passive"))
      (node (ref "C16") (pin "2") (pinfunction "2_2") (pintype "passive"))
      (node (ref "C17") (pin "2") (pinfunction "2_2") (pintype "passive"))
      (node (ref "C18") (pin "2") (pinfunction "2_2") (pintype "passive"))
      (node (ref "C19") (pin "2") (pinfunction "2_2") (pintype "passive"))
      (node (ref "C2") (pin "2") (pinfunction "2_2") (pintype "passive"))
      (node (ref "C20") (pin "2") (pinfunction "2_2") (pintype "passive"))
      (node (ref "C21") (pin "2") (pinfunction "2_2") (pintype "passive"))
      (node (ref "C3") (pin "2") (pinfunction "2_2") (pintype "passive"))
      (node (ref "C35") (pin "2") (pinfunction "2_2") (pintype "passive"))
      (node (ref "C4") (pin "2") (pinfunction "2_2") (pintype "passive"))
      (node (ref "C5") (pin "2") (pinfunction "2_2") (pintype "passive"))
      (node (ref "C6") (pin "2") (pinfunction "2_2") (pintype "passive"))
      (node (ref "C7") (pin "2") (pinfunction "2_2") (pintype "passive"))
      (node (ref "TP7") (pin "1") (pinfunction "1_1") (pintype "passive"))
      (node (ref "U1") (pin "B3") (pinfunction "VDDIO_B3") (pintype "power_in"))
      (node (ref "U1") (pin "B7") (pinfunction "VDDC_B7") (pintype "power_in"))
      (node (ref "U1") (pin "C3") (pinfunction "VDDIO_C3") (pintype "power_in"))
      (node (ref "U1") (pin "C7") (pinfunction "VDDC_C7") (pintype "power_in"))
      (node (ref "U1") (pin "D3") (pinfunction "VDDIO_D3") (pintype "power_in"))
      (node (ref "U1") (pin "D7") (pinfunction "VDDC_D7") (pintype "power_in"))
      (node (ref "U1") (pin "E3") (pinfunction "VDDIO_E3") (pintype "power_in"))
      (node (ref "U1") (pin "E7") (pinfunction "VDDC_E7") (pintype "power_in"))
      (node (ref "U1") (pin "F3") (pinfunction "VDDIO_F3") (pintype "power_in"))
      (node (ref "U1") (pin "F7") (pinfunction "VDDC_F7") (pintype "power_in"))
      (node (ref "U1") (pin "G3") (pinfunction "VDDIO_G3") (pintype "power_in"))
      (node (ref "U1") (pin "G7") (pinfunction "VDDC_G7") (pintype "power_in"))
      (node (ref "U1") (pin "H3") (pinfunction "VDDIO_H3") (pintype "power_in"))
      (node (ref "U1") (pin "H7") (pinfunction "VDDC_H7") (pintype "power_in"))
      (node (ref "U1") (pin "J3") (pinfunction "VDDIO_J3") (pintype "power_in"))
      (node (ref "U1") (pin "J7") (pinfunction "VDDC_J7") (pintype "power_in"))
      (node (ref "U1") (pin "K3") (pinfunction "VDDIO_K3") (pintype "power_in"))
      (node (ref "U1") (pin "K7") (pinfunction "VDDC_K7") (pintype "power_in"))
      (node (ref "U1") (pin "M7") (pinfunction "VDDC_M7") (pintype "power_in"))
      (node (ref "UP4") (pin "5") (pinfunction "VOUT_5") (pintype "input"))
    )
    (net (code "52") (name "unconnected-(H1-Pad0)") (class "Default")
      (node (ref "H1") (pin "0") (pinfunction "0_0") (pintype "passive"))
    )
    (net (code "53") (name "unconnected-(H2-Pad0)") (class "Default")
      (node (ref "H2") (pin "0") (pinfunction "0_0") (pintype "passive"))
    )
    (net (code "54") (name "unconnected-(H3-Pad0)") (class "Default")
      (node (ref "H3") (pin "0") (pinfunction "0_0") (pintype "passive"))
    )
    (net (code "55") (name "unconnected-(H4-Pad0)") (class "Default")
      (node (ref "H4") (pin "0") (pinfunction "0_0") (pintype "passive"))
    )
    (net (code "56") (name "unconnected-(J1-Pad11)") (class "Default")
      (node (ref "J1") (pin "11") (pintype "passive+no_connect"))
    )
    (net (code "57") (name "unconnected-(J1-Pad13)") (class "Default")
      (node (ref "J1") (pin "13") (pintype "passive+no_connect"))
    )
    (net (code "58") (name "unconnected-(J1-Pad15)") (class "Default")
      (node (ref "J1") (pin "15") (pintype "passive+no_connect"))
    )
    (net (code "59") (name "unconnected-(U1D-IPHOTO-PadK13)") (class "Default")
      (node (ref "U1") (pin "K13") (pinfunction "IPHOTO_K13") (pintype "bidirectional+no_connect"))
    )
    (net (code "60") (name "unconnected-(U1D-REFR_CLK-PadG13)") (class "Default")
      (node (ref "U1") (pin "G13") (pinfunction "REFR_CLK_G13") (pintype "output+no_connect"))
    )
    (net (code "61") (name "unconnected-(U1D-TPA1-PadA11)") (class "Default")
      (node (ref "U1") (pin "A11") (pinfunction "TPA1_A11") (pintype "bidirectional+no_connect"))
    )
    (net (code "62") (name "unconnected-(U1D-TPA2-PadA12)") (class "Default")
      (node (ref "U1") (pin "A12") (pinfunction "TPA2_A12") (pintype "bidirectional+no_connect"))
    )
    (net (code "63") (name "unconnected-(U1D-TPA3-PadA13)") (class "Default")
      (node (ref "U1") (pin "A13") (pinfunction "TPA3_A13") (pintype "bidirectional+no_connect"))
    )
    (net (code "64") (name "unconnected-(U1D-TPA4-PadB13)") (class "Default")
      (node (ref "U1") (pin "B13") (pinfunction "TPA4_B13") (pintype "bidirectional+no_connect"))
    )
    (net (code "65") (name "unconnected-(U1D-TPD1-PadA7)") (class "Default")
      (node (ref "U1") (pin "A7") (pinfunction "TPD1_A7") (pintype "output+no_connect"))
    )
    (net (code "66") (name "unconnected-(U1D-TPD2-PadA8)") (class "Default")
      (node (ref "U1") (pin "A8") (pinfunction "TPD2_A8") (pintype "output+no_connect"))
    )
    (net (code "67") (name "unconnected-(UP2-NC-Pad4)") (class "Default")
      (node (ref "UP2") (pin "4") (pinfunction "NC_4") (pintype "input+no_connect"))
    )
    (net (code "68") (name "unconnected-(UP3-NC-Pad4)") (class "Default")
      (node (ref "UP3") (pin "4") (pinfunction "NC_4") (pintype "input+no_connect"))
    )
    (net (code "69") (name "unconnected-(UP4-NC-Pad4)") (class "Default")
      (node (ref "UP4") (pin "4") (pinfunction "NC_4") (pintype "input+no_connect"))
    )
  )
)
